# push_botton.net
KiCad netlist of a schematic drawn in Altium Designer
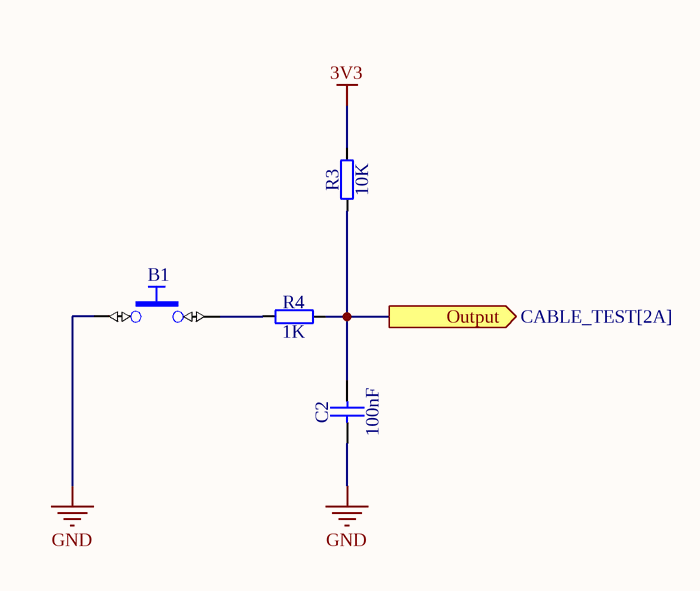
[diagram p0: push_botton.SchDoc]

(export (version "E")
  (design (tool "Eeschema 10.0.6"))
  (components
    (comp (ref "B1")
      (value "Push Button")
      (footprint "PB_TYCO_FSMSM")
      (description "Push-Button Switch SPST")
      (fields
        (field (name "PART NUMBER") "PB_TYCO_FSMSM")
        (field (name "MANUFACTURER") "TYCO ELECTRONICS")
        (field (name "AUTHOR") "CERN DEM JLC")
      )
      (libsource (lib "Eletro-mechanical") (part "PB SPST 1NO-2NO"))
    )
    (comp (ref "C2")
      (value "100nF")
      (footprint "CAPC2012X135N")
      (description "Non-polarised capacitor")
      (fields
        (field (name "PART NUMBER") "CC0805_100NF_50V_10%_X7R")
        (field (name "VOLTAGE") "50V")
        (field (name "AUTHOR") "CERN DEM JLC")
      )
      (libsource (lib "Capacitors") (part "Capacitor - non polarized"))
    )
    (comp (ref "R3")
      (value "10K")
      (footprint "RESC2012X60N")
      (description "Resistor - 1%")
      (fields
        (field (name "PART NUMBER") "R0805_24K_1%_0.125W_100PPM")
        (field (name "POWER") "0.125W")
        (field (name "AUTHOR") "CERN DEM JLC")
      )
      (libsource (lib "Resistors") (part "Resistor - 1%"))
    )
    (comp (ref "R4")
      (value "1K")
      (footprint "RESC2012X60N")
      (description "Resistor - 1%")
      (fields
        (field (name "PART NUMBER") "R0805_24K_1%_0.125W_100PPM")
        (field (name "POWER") "0.125W")
        (field (name "AUTHOR") "CERN DEM JLC")
      )
      (libsource (lib "Resistors") (part "Resistor - 1%"))
    )
  )
  (nets
    (net (code "1") (name "/Output") (class "Default")
      (node (ref "C2") (pin "2") (pinfunction "2_2") (pintype "passive"))
      (node (ref "R3") (pin "1") (pinfunction "1_1") (pintype "passive"))
      (node (ref "R4") (pin "2") (pinfunction "2_2") (pintype "passive"))
    )
    (net (code "2") (name "3V3") (class "Default")
      (node (ref "R3") (pin "2") (pinfunction "2_2") (pintype "passive"))
    )
    (net (code "3") (name "GND") (class "Default")
      (node (ref "B1") (pin "1") (pinfunction "1_1") (pintype "bidirectional"))
      (node (ref "C2") (pin "1") (pinfunction "1_1") (pintype "passive"))
    )
    (net (code "4") (name "Net-(B1-Pad2)") (class "Default")
      (node (ref "B1") (pin "2") (pinfunction "2_2") (pintype "bidirectional"))
      (node (ref "R4") (pin "1") (pinfunction "1_1") (pintype "passive"))
    )
  )
)
